# programming.net
KiCad netlist of a schematic drawn in Altium Designer
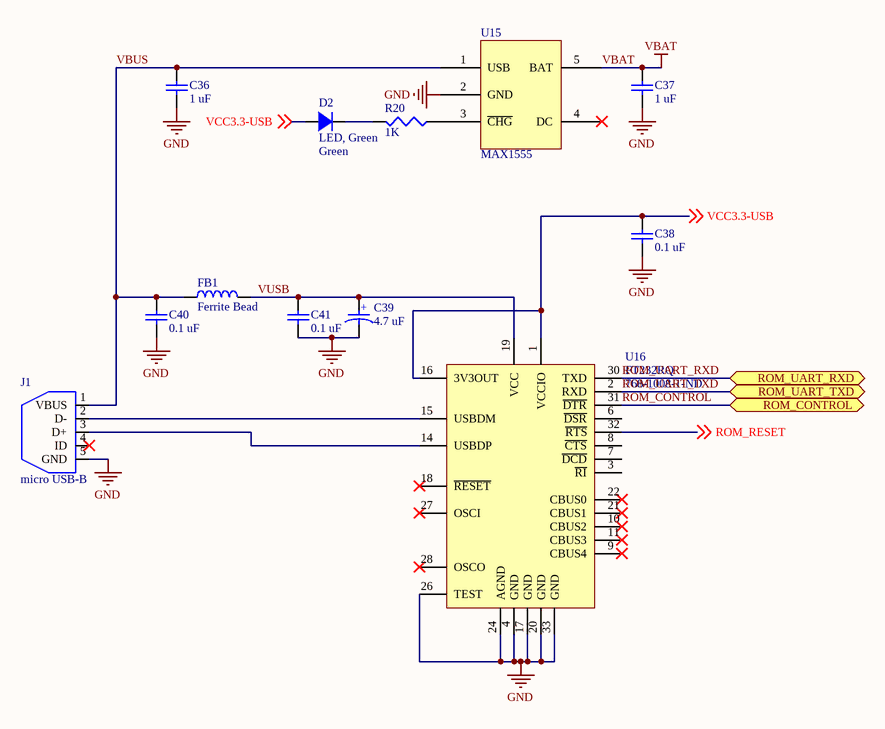
[diagram p0: programming.SchDoc]

(export (version "E")
  (design (tool "Eeschema 10.0.6"))
  (components
    (comp (ref "C36")
      (value "1 uF")
      (footprint "0402")
      (description "Ceramic capacitor, 1 uF, 0402 package")
      (fields (field (name "TOLERANCE") "10%") (field (name "Comment") "Ceramic capacitor"))
      (libsource (lib "rlc") (part "C_1u_0402_ceramic"))
    )
    (comp (ref "C37")
      (value "1 uF")
      (footprint "0402")
      (description "Ceramic capacitor, 1 uF, 0402 package")
      (fields (field (name "TOLERANCE") "10%") (field (name "Comment") "Ceramic capacitor"))
      (libsource (lib "rlc") (part "C_1u_0402_ceramic"))
    )
    (comp (ref "C38")
      (value "0.1 uF")
      (footprint "0402")
      (description "Ceramic capacitor, 0.1u, 0402 package")
      (fields (field (name "TOLERANCE") "10%") (field (name "Comment") "Ceramic capacitor"))
      (libsource (lib "rlc") (part "C_0.1u_0402_ceramic"))
    )
    (comp (ref "C39")
      (value "4.7 uF")
      (footprint "0603 - Polar Marking")
      (description "Tantalum capacitor, 4.7 uF, 0603 package")
      (fields (field (name "TOLERANCE") "20%") (field (name "Comment") "Tantalum capacitor"))
      (libsource (lib "rlc") (part "C_4.7u_0603_tantalum"))
    )
    (comp (ref "C40")
      (value "0.1 uF")
      (footprint "0402")
      (description "Ceramic capacitor, 0.1u, 0402 package")
      (fields (field (name "TOLERANCE") "10%") (field (name "Comment") "Ceramic capacitor"))
      (libsource (lib "rlc") (part "C_0.1u_0402_ceramic"))
    )
    (comp (ref "C41")
      (value "0.1 uF")
      (footprint "0402")
      (description "Ceramic capacitor, 0.1u, 0402 package")
      (fields (field (name "TOLERANCE") "10%") (field (name "Comment") "Ceramic capacitor"))
      (libsource (lib "rlc") (part "C_0.1u_0402_ceramic"))
    )
    (comp (ref "D2")
      (value "LED, Green")
      (footprint "0402 - DIODE")
      (description "LED, Green,  0402")
      (fields (field (name "COLOR") "Green"))
      (libsource (lib "rlc") (part "D_LED_GREEN_0402"))
    )
    (comp (ref "FB1")
      (value "Ferrite Bead")
      (footprint "0402")
      (description "Ferrite Bead, 150 mA, 0402 package")
      (libsource (lib "rlc") (part "FB_150mA_0402"))
    )
    (comp (ref "J1")
      (value "micro USB-B")
      (footprint "Micro USB-B")
      (description "CONN USB MICRO B RECPT SMT R/A")
      (libsource (lib "opo_general") (part "Micro USB"))
    )
    (comp (ref "R20")
      (value "1K")
      (footprint "0402")
      (description "Chip resistor, 1K, 0402 package")
      (fields (field (name "TOLERANCE") "1%") (field (name "POWER") "1/16 W"))
      (libsource (lib "rlc") (part "R_1K_0402"))
    )
    (comp (ref "U15")
      (value "MAX1555")
      (footprint "SOT23-5")
      (description "3 Dual-Input USB/AC Adapter 1-Cell Li+  Battery Chargers")
      (libsource (lib "opo_general") (part "MAX1555"))
    )
    (comp (ref "U16")
      (value "FT232RQ")
      (footprint "QFN-32")
      (description "FT232R USB UART")
      (fields (field (name "SUPPLIER PART NUMBER 1") "768-1008-1-ND"))
      (libsource (lib "opo_general") (part "IC_FT232RQ"))
    )
  )
  (nets
    (net (code "1") (name "/ROM_CONTROL") (class "Default")
      (node (ref "U16") (pin "31") (pinfunction "~{DTR}_31") (pintype "passive"))
    )
    (net (code "2") (name "/ROM_UART_RXD") (class "Default")
      (node (ref "U16") (pin "30") (pinfunction "TXD_30") (pintype "passive"))
    )
    (net (code "3") (name "/ROM_UART_TXD") (class "Default")
      (node (ref "U16") (pin "2") (pinfunction "RXD_2") (pintype "passive"))
    )
    (net (code "4") (name "/VBUS") (class "Default")
      (node (ref "C36") (pin "1") (pintype "passive"))
      (node (ref "C40") (pin "1") (pintype "passive"))
      (node (ref "FB1") (pin "2") (pintype "passive"))
      (node (ref "J1") (pin "1") (pinfunction "VBUS_1") (pintype "power_in"))
      (node (ref "U15") (pin "1") (pinfunction "USB_1") (pintype "passive"))
    )
    (net (code "5") (name "/VUSB") (class "Default")
      (node (ref "C39") (pin "1") (pintype "passive"))
      (node (ref "C41") (pin "1") (pintype "passive"))
      (node (ref "FB1") (pin "1") (pintype "passive"))
      (node (ref "U16") (pin "19") (pinfunction "VCC_19") (pintype "passive"))
    )
    (net (code "6") (name "GND") (class "Default")
      (node (ref "C36") (pin "2") (pintype "passive"))
      (node (ref "C37") (pin "2") (pintype "passive"))
      (node (ref "C38") (pin "2") (pintype "passive"))
      (node (ref "C39") (pin "2") (pintype "passive"))
      (node (ref "C40") (pin "2") (pintype "passive"))
      (node (ref "C41") (pin "2") (pintype "passive"))
      (node (ref "J1") (pin "5") (pinfunction "GND_5") (pintype "power_in"))
      (node (ref "U15") (pin "2") (pinfunction "GND_2") (pintype "passive"))
      (node (ref "U16") (pin "17") (pinfunction "GND_17") (pintype "passive"))
      (node (ref "U16") (pin "20") (pinfunction "GND_20") (pintype "passive"))
      (node (ref "U16") (pin "24") (pinfunction "AGND_24") (pintype "passive"))
      (node (ref "U16") (pin "26") (pinfunction "TEST_26") (pintype "passive"))
      (node (ref "U16") (pin "33") (pinfunction "GND_33") (pintype "passive"))
      (node (ref "U16") (pin "4") (pinfunction "GND_4") (pintype "passive"))
    )
    (net (code "7") (name "Net-(D2-Pad2)") (class "Default")
      (node (ref "D2") (pin "2") (pintype "passive"))
      (node (ref "R20") (pin "1") (pintype "passive"))
    )
    (net (code "8") (name "Net-(J1-D+)") (class "Default")
      (node (ref "J1") (pin "3") (pinfunction "D+_3") (pintype "power_in"))
      (node (ref "U16") (pin "14") (pinfunction "USBDP_14") (pintype "passive"))
    )
    (net (code "9") (name "Net-(J1-D-)") (class "Default")
      (node (ref "J1") (pin "2") (pinfunction "D-_2") (pintype "power_in"))
      (node (ref "U16") (pin "15") (pinfunction "USBDM_15") (pintype "passive"))
    )
    (net (code "10") (name "Net-(U15-~{CHG})") (class "Default")
      (node (ref "R20") (pin "2") (pintype "passive"))
      (node (ref "U15") (pin "3") (pinfunction "~{CHG}_3") (pintype "passive"))
    )
    (net (code "11") (name "ROM_RESET") (class "Default")
      (node (ref "U16") (pin "32") (pinfunction "~{RTS}_32") (pintype "passive"))
    )
    (net (code "12") (name "VBAT") (class "Default")
      (node (ref "C37") (pin "1") (pintype "passive"))
      (node (ref "U15") (pin "5") (pinfunction "BAT_5") (pintype "passive"))
    )
    (net (code "13") (name "VCC3.3-USB") (class "Default")
      (node (ref "C38") (pin "1") (pintype "passive"))
      (node (ref "D2") (pin "1") (pintype "passive"))
      (node (ref "U16") (pin "1") (pinfunction "VCCIO_1") (pintype "passive"))
      (node (ref "U16") (pin "16") (pinfunction "3V3OUT_16") (pintype "passive"))
    )
    (net (code "14") (name "unconnected-(J1-ID-Pad4)") (class "Default")
      (node (ref "J1") (pin "4") (pinfunction "ID_4") (pintype "power_in+no_connect"))
    )
    (net (code "15") (name "unconnected-(U15-DC-Pad4)") (class "Default")
      (node (ref "U15") (pin "4") (pinfunction "DC_4") (pintype "passive+no_connect"))
    )
    (net (code "16") (name "unconnected-(U16-CBUS0-Pad22)") (class "Default")
      (node (ref "U16") (pin "22") (pinfunction "CBUS0_22") (pintype "passive+no_connect"))
    )
    (net (code "17") (name "unconnected-(U16-CBUS1-Pad21)") (class "Default")
      (node (ref "U16") (pin "21") (pinfunction "CBUS1_21") (pintype "passive+no_connect"))
    )
    (net (code "18") (name "unconnected-(U16-CBUS2-Pad10)") (class "Default")
      (node (ref "U16") (pin "10") (pinfunction "CBUS2_10") (pintype "passive+no_connect"))
    )
    (net (code "19") (name "unconnected-(U16-CBUS3-Pad11)") (class "Default")
      (node (ref "U16") (pin "11") (pinfunction "CBUS3_11") (pintype "passive+no_connect"))
    )
    (net (code "20") (name "unconnected-(U16-CBUS4-Pad9)") (class "Default")
      (node (ref "U16") (pin "9") (pinfunction "CBUS4_9") (pintype "passive+no_connect"))
    )
    (net (code "21") (name "unconnected-(U16-OSCI-Pad27)") (class "Default")
      (node (ref "U16") (pin "27") (pinfunction "OSCI_27") (pintype "passive+no_connect"))
    )
    (net (code "22") (name "unconnected-(U16-OSCO-Pad28)") (class "Default")
      (node (ref "U16") (pin "28") (pinfunction "OSCO_28") (pintype "passive+no_connect"))
    )
    (net (code "23") (name "unconnected-(U16-~{CTS}-Pad8)") (class "Default")
      (node (ref "U16") (pin "8") (pinfunction "~{CTS}_8") (pintype "passive"))
    )
    (net (code "24") (name "unconnected-(U16-~{DCD}-Pad7)") (class "Default")
      (node (ref "U16") (pin "7") (pinfunction "~{DCD}_7") (pintype "passive"))
    )
    (net (code "25") (name "unconnected-(U16-~{DSR}-Pad6)") (class "Default")
      (node (ref "U16") (pin "6") (pinfunction "~{DSR}_6") (pintype "passive"))
    )
    (net (code "26") (name "unconnected-(U16-~{RESET}-Pad18)") (class "Default")
      (node (ref "U16") (pin "18") (pinfunction "~{RESET}_18") (pintype "passive+no_connect"))
    )
    (net (code "27") (name "unconnected-(U16-~{RI}-Pad3)") (class "Default")
      (node (ref "U16") (pin "3") (pinfunction "~{RI}_3") (pintype "passive"))
    )
  )
)
